# Cycle-Controller-Onboard.net
KiCad netlist of a schematic drawn in Altium Designer
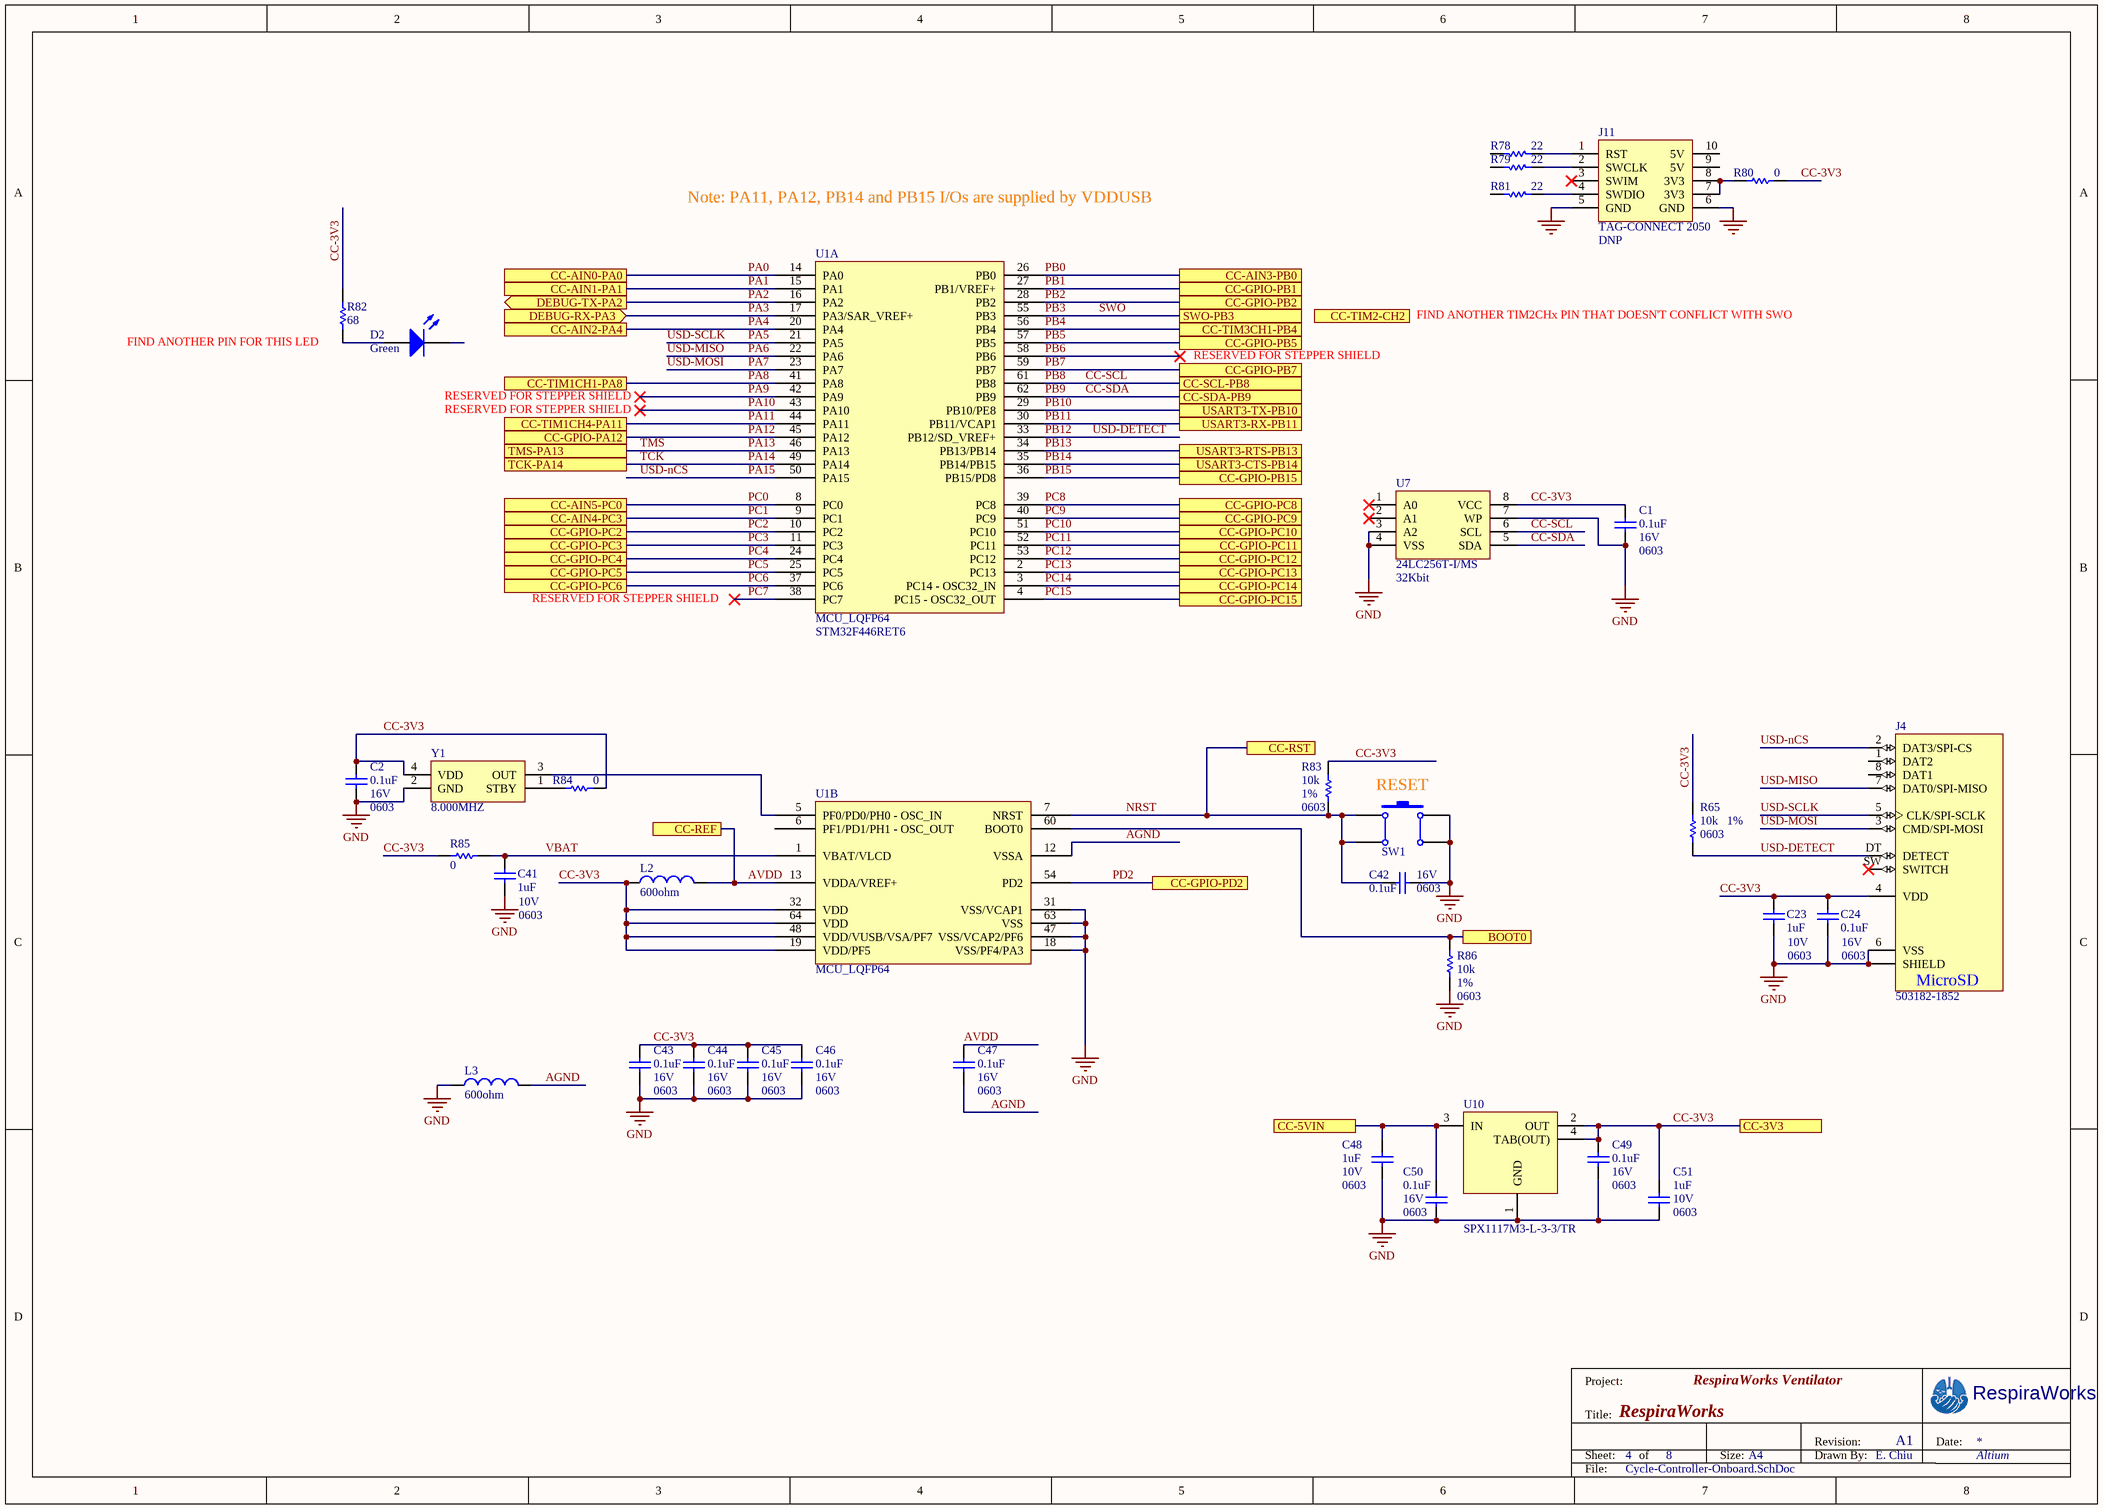
[diagram p0: Cycle-Controller-Onboard.SchDoc]

(export (version "E")
  (design (tool "Eeschema 10.0.6"))
  (components
    (comp (ref "C1")
      (value "0.1uF")
      (footprint "CAP0603")
      (description "Cap 0603")
      (fields
        (field (name "MANUFACTURER") "Yageo")
        (field (name "VOLTAGE") "16V")
        (field (name "PCB PACKAGE") "0603")
        (field (name "Comment") "CAP 0603")
      )
      (libsource (lib "generic") (part "CAP 0603"))
    )
    (comp (ref "C2")
      (value "0.1uF")
      (footprint "CAP0603")
      (description "Cap 0603")
      (fields
        (field (name "MANUFACTURER") "Yageo")
        (field (name "VOLTAGE") "16V")
        (field (name "PCB PACKAGE") "0603")
        (field (name "Comment") "CAP 0603")
      )
      (libsource (lib "generic") (part "CAP 0603"))
    )
    (comp (ref "C23")
      (value "1uF")
      (footprint "CAP0603")
      (description "Cap 0603")
      (fields
        (field (name "MANUFACTURER") "Yageo")
        (field (name "VOLTAGE") "10V")
        (field (name "PCB PACKAGE") "0603")
        (field (name "Comment") "CAP 0603")
      )
      (libsource (lib "generic") (part "CAP 0603"))
    )
    (comp (ref "C24")
      (value "0.1uF")
      (footprint "CAP0603")
      (description "Cap 0603")
      (fields
        (field (name "MANUFACTURER") "Yageo")
        (field (name "VOLTAGE") "16V")
        (field (name "PCB PACKAGE") "0603")
        (field (name "Comment") "CAP 0603")
      )
      (libsource (lib "generic") (part "CAP 0603"))
    )
    (comp (ref "C41")
      (value "1uF")
      (footprint "CAP0603")
      (description "Cap 0603")
      (fields
        (field (name "MANUFACTURER") "Yageo")
        (field (name "VOLTAGE") "10V")
        (field (name "PCB PACKAGE") "0603")
        (field (name "Comment") "CAP 0603")
      )
      (libsource (lib "generic") (part "CAP 0603"))
    )
    (comp (ref "C42")
      (value "0.1uF")
      (footprint "CAP0603")
      (description "Cap 0603")
      (fields
        (field (name "MANUFACTURER") "Yageo")
        (field (name "VOLTAGE") "16V")
        (field (name "PCB PACKAGE") "0603")
        (field (name "Comment") "CAP 0603")
      )
      (libsource (lib "generic") (part "CAP 0603"))
    )
    (comp (ref "C43")
      (value "0.1uF")
      (footprint "CAP0603")
      (description "Cap 0603")
      (fields
        (field (name "MANUFACTURER") "Yageo")
        (field (name "VOLTAGE") "16V")
        (field (name "PCB PACKAGE") "0603")
        (field (name "Comment") "CAP 0603")
      )
      (libsource (lib "generic") (part "CAP 0603"))
    )
    (comp (ref "C44")
      (value "0.1uF")
      (footprint "CAP0603")
      (description "Cap 0603")
      (fields
        (field (name "MANUFACTURER") "Yageo")
        (field (name "VOLTAGE") "16V")
        (field (name "PCB PACKAGE") "0603")
        (field (name "Comment") "CAP 0603")
      )
      (libsource (lib "generic") (part "CAP 0603"))
    )
    (comp (ref "C45")
      (value "0.1uF")
      (footprint "CAP0603")
      (description "Cap 0603")
      (fields
        (field (name "MANUFACTURER") "Yageo")
        (field (name "VOLTAGE") "16V")
        (field (name "PCB PACKAGE") "0603")
        (field (name "Comment") "CAP 0603")
      )
      (libsource (lib "generic") (part "CAP 0603"))
    )
    (comp (ref "C46")
      (value "0.1uF")
      (footprint "CAP0603")
      (description "Cap 0603")
      (fields
        (field (name "MANUFACTURER") "Yageo")
        (field (name "VOLTAGE") "16V")
        (field (name "PCB PACKAGE") "0603")
        (field (name "Comment") "CAP 0603")
      )
      (libsource (lib "generic") (part "CAP 0603"))
    )
    (comp (ref "C47")
      (value "0.1uF")
      (footprint "CAP0603")
      (description "Cap 0603")
      (fields
        (field (name "MANUFACTURER") "Yageo")
        (field (name "VOLTAGE") "16V")
        (field (name "PCB PACKAGE") "0603")
        (field (name "Comment") "CAP 0603")
      )
      (libsource (lib "generic") (part "CAP 0603"))
    )
    (comp (ref "C48")
      (value "1uF")
      (footprint "CAP0603")
      (description "Cap 0603")
      (fields
        (field (name "MANUFACTURER") "Yageo")
        (field (name "VOLTAGE") "10V")
        (field (name "PCB PACKAGE") "0603")
        (field (name "Comment") "CAP 0603")
      )
      (libsource (lib "generic") (part "CAP 0603"))
    )
    (comp (ref "C49")
      (value "0.1uF")
      (footprint "CAP0603")
      (description "Cap 0603")
      (fields
        (field (name "MANUFACTURER") "Yageo")
        (field (name "VOLTAGE") "16V")
        (field (name "PCB PACKAGE") "0603")
        (field (name "Comment") "CAP 0603")
      )
      (libsource (lib "generic") (part "CAP 0603"))
    )
    (comp (ref "C50")
      (value "0.1uF")
      (footprint "CAP0603")
      (description "Cap 0603")
      (fields
        (field (name "MANUFACTURER") "Yageo")
        (field (name "VOLTAGE") "16V")
        (field (name "PCB PACKAGE") "0603")
        (field (name "Comment") "CAP 0603")
      )
      (libsource (lib "generic") (part "CAP 0603"))
    )
    (comp (ref "C51")
      (value "1uF")
      (footprint "CAP0603")
      (description "Cap 0603")
      (fields
        (field (name "MANUFACTURER") "Yageo")
        (field (name "VOLTAGE") "10V")
        (field (name "PCB PACKAGE") "0603")
        (field (name "Comment") "CAP 0603")
      )
      (libsource (lib "generic") (part "CAP 0603"))
    )
    (comp (ref "D2")
      (value "Green")
      (footprint "LED0603")
      (description "LED 0603")
      (fields (field (name "MANUFACTURER") "Lite-On"))
      (libsource (lib "generic") (part "LED 0603"))
    )
    (comp (ref "J4")
      (value "503182-1852")
      (footprint "molex:503182-1852")
      (description "10 _8 + 2_ Position Card Connector microSD Surface Mount, Right Angle Gold")
      (fields (field (name "MANUFACTURER") "Molex") (field (name "DIGI-KEY_PART_NUMBER") "WM12834CT-ND"))
      (libsource (lib "molex") (part "503182-1852"))
    )
    (comp (ref "J11")
      (value "TAG-CONNECT 2050")
      (footprint "TAG-CONNECT-2050")
      (description "10-pin TAG-CONNECT Bed of Nails footprint")
      (fields (field (name "MANUFACTURER") "TAG-CONNECT") (field (name "DO NOT POPULATE") "DNP"))
      (libsource (lib "special") (part "TC-2050-STLINK"))
    )
    (comp (ref "L2")
      (value "600ohm")
      (footprint "IND0603")
      (description "Ferrite 0603")
      (fields (field (name "MANUFACTURER") "Wurth") (field (name "Comment") "BEAD"))
      (libsource (lib "generic") (part "FERRITE 0603"))
    )
    (comp (ref "L3")
      (value "600ohm")
      (footprint "IND0603")
      (description "Ferrite 0603")
      (fields (field (name "MANUFACTURER") "Wurth") (field (name "Comment") "BEAD"))
      (libsource (lib "generic") (part "FERRITE 0603"))
    )
    (comp (ref "R65")
      (value "10k")
      (footprint "RES0603")
      (description "Res 0603")
      (fields
        (field (name "MANUFACTURER") "Panasonic")
        (field (name "PCB PACKAGE") "0603")
        (field (name "TOLERANCE") "1%")
        (field (name "Comment") "RES 0603")
      )
      (libsource (lib "generic") (part "RES 0603"))
    )
    (comp (ref "R78")
      (value "22")
      (footprint "RES0603")
      (description "Res 0603")
      (fields (field (name "MANUFACTURER") "Yageo") (field (name "TOLERANCE") "1%"))
      (libsource (lib "generic") (part "RES 0603"))
    )
    (comp (ref "R79")
      (value "22")
      (footprint "RES0603")
      (description "Res 0603")
      (fields (field (name "MANUFACTURER") "Yageo") (field (name "TOLERANCE") "1%"))
      (libsource (lib "generic") (part "RES 0603"))
    )
    (comp (ref "R80")
      (value "0")
      (footprint "RES0603")
      (description "Res 0603")
      (fields (field (name "MANUFACTURER") "Panasonic") (field (name "Comment") "RES 0603"))
      (libsource (lib "generic") (part "RES 0603"))
    )
    (comp (ref "R81")
      (value "22")
      (footprint "RES0603")
      (description "Res 0603")
      (fields (field (name "MANUFACTURER") "Yageo") (field (name "TOLERANCE") "1%"))
      (libsource (lib "generic") (part "RES 0603"))
    )
    (comp (ref "R82")
      (value "68")
      (footprint "RES0603")
      (description "Res 0603")
      (fields (field (name "MANUFACTURER") "Panasonic") (field (name "TOLERANCE") "1%"))
      (libsource (lib "generic") (part "RES 0603"))
    )
    (comp (ref "R83")
      (value "10k")
      (footprint "RES0603")
      (description "Res 0603")
      (fields
        (field (name "MANUFACTURER") "Panasonic")
        (field (name "PCB PACKAGE") "0603")
        (field (name "TOLERANCE") "1%")
        (field (name "Comment") "RES 0603")
      )
      (libsource (lib "generic") (part "RES 0603"))
    )
    (comp (ref "R84")
      (value "0")
      (footprint "RES0603")
      (description "Res 0603")
      (fields (field (name "MANUFACTURER") "Panasonic") (field (name "Comment") "RES 0603"))
      (libsource (lib "generic") (part "RES 0603"))
    )
    (comp (ref "R85")
      (value "0")
      (footprint "RES0603")
      (description "Res 0603")
      (fields (field (name "MANUFACTURER") "Panasonic") (field (name "Comment") "RES 0603"))
      (libsource (lib "generic") (part "RES 0603"))
    )
    (comp (ref "R86")
      (value "10k")
      (footprint "RES0603")
      (description "Res 0603")
      (fields
        (field (name "MANUFACTURER") "Panasonic")
        (field (name "PCB PACKAGE") "0603")
        (field (name "TOLERANCE") "1%")
        (field (name "Comment") "RES 0603")
      )
      (libsource (lib "generic") (part "RES 0603"))
    )
    (comp (ref "SW1")
      (value "BUTTON")
      (footprint "PB-6MM-J-LEAD")
      (description "PUSHBUTTON, 6MM SQ, TACT, J-Lead")
      (fields (field (name "MANUFACTURER") "E-Switch"))
      (libsource (lib "e-switch") (part "PUSHBUTTON-SQ-6MM-TACT-J-LEAD"))
    )
    (comp (ref "U1")
      (value "MCU_LQFP64")
      (footprint "64-LQFP")
      (description "IC MCU 32BIT 512KB FLASH 64LQFP")
      (fields (field (name "MANUFACTURER P/N") "STM32F446RET6") (field (name "MANUFACTURER") "ST Micro"))
      (libsource (lib "Nucleo_64") (part "MCU_LQFP64"))
    )
    (comp (ref "U7")
      (value "32Kbit")
      (footprint "8-MSOP")
      (description "IC EEPROM 256KBIT I2C 400KHZ 8MSOP")
      (fields
        (field (name "MANUFACTURER") "Microchip")
        (field (name "TOLERANCE") "25ppm")
        (field (name "MANUFACTURER P/N") "24LC256T-I/MS")
      )
      (libsource (lib "microchip") (part "24LC256T-I/MS"))
    )
    (comp (ref "U10")
      (value "NCP1117ST33T3G")
      (footprint "3-SOT223")
      (description "LDO, 3.3V out, 1A, 20V in, SOT-223, 0.8W Pd max")
      (fields (field (name "MANUFACTURER") "Exar") (field (name "MANUFACTURER P/N") "SPX1117M3-L-3-3/TR"))
      (libsource (lib "on-semi") (part "NCP1117ST33T3G"))
    )
    (comp (ref "Y1")
      (value "8.000MHZ")
      (footprint "4-OSC3225")
      (description "OSC MEMS 8.000MHZ CMOS SMD")
      (fields (field (name "MANUFACTURER") "Abracon") (field (name "TOLERANCE") "50ppm"))
      (libsource (lib "abracon") (part "ASEMB-8.000MHZ-LC-T"))
    )
  )
  (nets
    (net (code "1") (name "/AGND") (class "Default")
      (node (ref "C47") (pin "2") (pinfunction "2_2") (pintype "passive"))
      (node (ref "L3") (pin "2") (pinfunction "2_2") (pintype "passive"))
      (node (ref "U1") (pin "12") (pinfunction "VSSA_12") (pintype "passive"))
    )
    (net (code "2") (name "/AVDD") (class "Default")
      (node (ref "C47") (pin "1") (pinfunction "1_1") (pintype "passive"))
      (node (ref "L2") (pin "2") (pinfunction "2_2") (pintype "passive"))
      (node (ref "U1") (pin "13") (pinfunction "VDDA/VREF+_13") (pintype "passive"))
    )
    (net (code "3") (name "/BOOT0") (class "Default")
      (node (ref "R86") (pin "2") (pinfunction "2_2") (pintype "passive"))
      (node (ref "U1") (pin "60") (pinfunction "BOOT0_60") (pintype "passive"))
    )
    (net (code "4") (name "/CC-3V3") (class "Default")
      (node (ref "C1") (pin "1") (pinfunction "1_1") (pintype "passive"))
      (node (ref "C2") (pin "1") (pinfunction "1_1") (pintype "passive"))
      (node (ref "C23") (pin "1") (pinfunction "1_1") (pintype "passive"))
      (node (ref "C24") (pin "1") (pinfunction "1_1") (pintype "passive"))
      (node (ref "C43") (pin "1") (pinfunction "1_1") (pintype "passive"))
      (node (ref "C44") (pin "1") (pinfunction "1_1") (pintype "passive"))
      (node (ref "C45") (pin "1") (pinfunction "1_1") (pintype "passive"))
      (node (ref "C46") (pin "1") (pinfunction "1_1") (pintype "passive"))
      (node (ref "C49") (pin "1") (pinfunction "1_1") (pintype "passive"))
      (node (ref "C51") (pin "1") (pinfunction "1_1") (pintype "passive"))
      (node (ref "J4") (pin "4") (pinfunction "VDD_4") (pintype "power_in"))
      (node (ref "L2") (pin "1") (pinfunction "1_1") (pintype "passive"))
      (node (ref "R65") (pin "2") (pinfunction "2_2") (pintype "passive"))
      (node (ref "R80") (pin "2") (pinfunction "2_2") (pintype "passive"))
      (node (ref "R82") (pin "2") (pinfunction "2_2") (pintype "passive"))
      (node (ref "R83") (pin "2") (pinfunction "2_2") (pintype "passive"))
      (node (ref "R84") (pin "1") (pinfunction "1_1") (pintype "passive"))
      (node (ref "R85") (pin "2") (pinfunction "2_2") (pintype "passive"))
      (node (ref "U1") (pin "19") (pinfunction "VDD/PF5_19") (pintype "passive"))
      (node (ref "U1") (pin "32") (pinfunction "VDD_32") (pintype "passive"))
      (node (ref "U1") (pin "48") (pinfunction "VDD/VUSB/VSA/PF7_48") (pintype "passive"))
      (node (ref "U1") (pin "64") (pinfunction "VDD_64") (pintype "passive"))
      (node (ref "U10") (pin "2") (pinfunction "OUT_2") (pintype "passive"))
      (node (ref "U10") (pin "4") (pinfunction "TAB(OUT)_4") (pintype "passive"))
      (node (ref "U7") (pin "8") (pinfunction "VCC_8") (pintype "passive"))
      (node (ref "Y1") (pin "4") (pinfunction "VDD_4") (pintype "passive"))
    )
    (net (code "5") (name "/CC-5VIN") (class "Default")
      (node (ref "C48") (pin "1") (pinfunction "1_1") (pintype "passive"))
      (node (ref "C50") (pin "1") (pinfunction "1_1") (pintype "passive"))
      (node (ref "U10") (pin "3") (pinfunction "IN_3") (pintype "passive"))
    )
    (net (code "6") (name "/CC-SCL") (class "Default")
      (node (ref "U1") (pin "61") (pinfunction "PB8_61") (pintype "passive"))
      (node (ref "U7") (pin "6") (pinfunction "SCL_6") (pintype "passive"))
    )
    (net (code "7") (name "/CC-SDA") (class "Default")
      (node (ref "U1") (pin "62") (pinfunction "PB9_62") (pintype "passive"))
      (node (ref "U7") (pin "5") (pinfunction "SDA_5") (pintype "passive"))
    )
    (net (code "9") (name "/NRST") (class "Default")
      (node (ref "C42") (pin "1") (pinfunction "1_1") (pintype "passive"))
      (node (ref "R83") (pin "1") (pinfunction "1_1") (pintype "passive"))
      (node (ref "SW1") (pin "1") (pinfunction "1_1") (pintype "passive"))
      (node (ref "SW1") (pin "2") (pinfunction "2_2") (pintype "passive"))
      (node (ref "U1") (pin "7") (pinfunction "NRST_7") (pintype "passive"))
    )
    (net (code "10") (name "/PA0") (class "Default")
      (node (ref "U1") (pin "14") (pinfunction "PA0_14") (pintype "passive"))
    )
    (net (code "11") (name "/PA1") (class "Default")
      (node (ref "U1") (pin "15") (pinfunction "PA1_15") (pintype "passive"))
    )
    (net (code "12") (name "/PA2") (class "Default")
      (node (ref "U1") (pin "16") (pinfunction "PA2_16") (pintype "passive"))
    )
    (net (code "13") (name "/PA3") (class "Default")
      (node (ref "U1") (pin "17") (pinfunction "PA3/SAR_VREF+_17") (pintype "passive"))
    )
    (net (code "14") (name "/PA4") (class "Default")
      (node (ref "U1") (pin "20") (pinfunction "PA4_20") (pintype "passive"))
    )
    (net (code "15") (name "/PA5") (class "Default")
      (node (ref "J4") (pin "5") (pinfunction "CLK/SPI-SCLK_5") (pintype "bidirectional"))
      (node (ref "U1") (pin "21") (pinfunction "PA5_21") (pintype "passive"))
    )
    (net (code "16") (name "/PA6") (class "Default")
      (node (ref "J4") (pin "7") (pinfunction "DAT0/SPI-MISO_7") (pintype "bidirectional"))
      (node (ref "U1") (pin "22") (pinfunction "PA6_22") (pintype "passive"))
    )
    (net (code "17") (name "/PA7") (class "Default")
      (node (ref "J4") (pin "3") (pinfunction "CMD/SPI-MOSI_3") (pintype "bidirectional"))
      (node (ref "U1") (pin "23") (pinfunction "PA7_23") (pintype "passive"))
    )
    (net (code "18") (name "/PA8") (class "Default")
      (node (ref "U1") (pin "41") (pinfunction "PA8_41") (pintype "passive"))
    )
    (net (code "19") (name "/PA9") (class "Default")
      (node (ref "U1") (pin "42") (pinfunction "PA9_42") (pintype "passive+no_connect"))
    )
    (net (code "20") (name "/PA10") (class "Default")
      (node (ref "U1") (pin "43") (pinfunction "PA10_43") (pintype "passive+no_connect"))
    )
    (net (code "21") (name "/PA11") (class "Default")
      (node (ref "U1") (pin "44") (pinfunction "PA11_44") (pintype "passive"))
    )
    (net (code "22") (name "/PA12") (class "Default")
      (node (ref "U1") (pin "45") (pinfunction "PA12_45") (pintype "passive"))
    )
    (net (code "23") (name "/PA13") (class "Default")
      (node (ref "U1") (pin "46") (pinfunction "PA13_46") (pintype "passive"))
    )
    (net (code "24") (name "/PA14") (class "Default")
      (node (ref "U1") (pin "49") (pinfunction "PA14_49") (pintype "passive"))
    )
    (net (code "25") (name "/PA15") (class "Default")
      (node (ref "J4") (pin "2") (pinfunction "DAT3/SPI-CS_2") (pintype "bidirectional"))
      (node (ref "U1") (pin "50") (pinfunction "PA15_50") (pintype "passive"))
    )
    (net (code "26") (name "/PB0") (class "Default")
      (node (ref "U1") (pin "26") (pinfunction "PB0_26") (pintype "passive"))
    )
    (net (code "27") (name "/PB1") (class "Default")
      (node (ref "U1") (pin "27") (pinfunction "PB1/VREF+_27") (pintype "passive"))
    )
    (net (code "28") (name "/PB2") (class "Default")
      (node (ref "U1") (pin "28") (pinfunction "PB2_28") (pintype "passive"))
    )
    (net (code "29") (name "/PB3") (class "Default")
      (node (ref "U1") (pin "55") (pinfunction "PB3_55") (pintype "passive"))
    )
    (net (code "30") (name "/PB4") (class "Default")
      (node (ref "U1") (pin "56") (pinfunction "PB4_56") (pintype "passive"))
    )
    (net (code "31") (name "/PB5") (class "Default")
      (node (ref "U1") (pin "57") (pinfunction "PB5_57") (pintype "passive"))
    )
    (net (code "32") (name "/PB6") (class "Default")
      (node (ref "U1") (pin "58") (pinfunction "PB6_58") (pintype "passive+no_connect"))
    )
    (net (code "33") (name "/PB7") (class "Default")
      (node (ref "U1") (pin "59") (pinfunction "PB7_59") (pintype "passive"))
    )
    (net (code "34") (name "/PB10") (class "Default")
      (node (ref "U1") (pin "29") (pinfunction "PB10/PE8_29") (pintype "passive"))
    )
    (net (code "35") (name "/PB11") (class "Default")
      (node (ref "U1") (pin "30") (pinfunction "PB11/VCAP1_30") (pintype "passive"))
    )
    (net (code "36") (name "/PB12") (class "Default")
      (node (ref "J4") (pin "DT") (pinfunction "DETECT_DT") (pintype "bidirectional"))
      (node (ref "R65") (pin "1") (pinfunction "1_1") (pintype "passive"))
      (node (ref "U1") (pin "33") (pinfunction "PB12/SD_VREF+_33") (pintype "passive"))
    )
    (net (code "37") (name "/PB13") (class "Default")
      (node (ref "U1") (pin "34") (pinfunction "PB13/PB14_34") (pintype "passive"))
    )
    (net (code "38") (name "/PB14") (class "Default")
      (node (ref "U1") (pin "35") (pinfunction "PB14/PB15_35") (pintype "passive"))
    )
    (net (code "39") (name "/PB15") (class "Default")
      (node (ref "U1") (pin "36") (pinfunction "PB15/PD8_36") (pintype "passive"))
    )
    (net (code "40") (name "/PC0") (class "Default")
      (node (ref "U1") (pin "8") (pinfunction "PC0_8") (pintype "passive"))
    )
    (net (code "41") (name "/PC1") (class "Default")
      (node (ref "U1") (pin "9") (pinfunction "PC1_9") (pintype "passive"))
    )
    (net (code "42") (name "/PC2") (class "Default")
      (node (ref "U1") (pin "10") (pinfunction "PC2_10") (pintype "passive"))
    )
    (net (code "43") (name "/PC3") (class "Default")
      (node (ref "U1") (pin "11") (pinfunction "PC3_11") (pintype "passive"))
    )
    (net (code "44") (name "/PC4") (class "Default")
      (node (ref "U1") (pin "24") (pinfunction "PC4_24") (pintype "passive"))
    )
    (net (code "45") (name "/PC5") (class "Default")
      (node (ref "U1") (pin "25") (pinfunction "PC5_25") (pintype "passive"))
    )
    (net (code "46") (name "/PC6") (class "Default")
      (node (ref "U1") (pin "37") (pinfunction "PC6_37") (pintype "passive"))
    )
    (net (code "47") (name "/PC7") (class "Default")
      (node (ref "U1") (pin "38") (pinfunction "PC7_38") (pintype "passive+no_connect"))
    )
    (net (code "48") (name "/PC8") (class "Default")
      (node (ref "U1") (pin "39") (pinfunction "PC8_39") (pintype "passive"))
    )
    (net (code "49") (name "/PC9") (class "Default")
      (node (ref "U1") (pin "40") (pinfunction "PC9_40") (pintype "passive"))
    )
    (net (code "50") (name "/PC10") (class "Default")
      (node (ref "U1") (pin "51") (pinfunction "PC10_51") (pintype "passive"))
    )
    (net (code "51") (name "/PC11") (class "Default")
      (node (ref "U1") (pin "52") (pinfunction "PC11_52") (pintype "passive"))
    )
    (net (code "52") (name "/PC12") (class "Default")
      (node (ref "U1") (pin "53") (pinfunction "PC12_53") (pintype "passive"))
    )
    (net (code "53") (name "/PC13") (class "Default")
      (node (ref "U1") (pin "2") (pinfunction "PC13_2") (pintype "passive"))
    )
    (net (code "54") (name "/PC14") (class "Default")
      (node (ref "U1") (pin "3") (pinfunction "PC14_-_OSC32_IN_3") (pintype "passive"))
    )
    (net (code "55") (name "/PC15") (class "Default")
      (node (ref "U1") (pin "4") (pinfunction "PC15_-_OSC32_OUT_4") (pintype "passive"))
    )
    (net (code "56") (name "/PD2") (class "Default")
      (node (ref "U1") (pin "54") (pinfunction "PD2_54") (pintype "passive"))
    )
    (net (code "57") (name "/VBAT") (class "Default")
      (node (ref "C41") (pin "1") (pinfunction "1_1") (pintype "passive"))
      (node (ref "R85") (pin "1") (pinfunction "1_1") (pintype "passive"))
      (node (ref "U1") (pin "1") (pinfunction "VBAT/VLCD_1") (pintype "passive"))
    )
    (net (code "58") (name "GND") (class "Default")
      (node (ref "C1") (pin "2") (pinfunction "2_2") (pintype "passive"))
      (node (ref "C2") (pin "2") (pinfunction "2_2") (pintype "passive"))
      (node (ref "C23") (pin "2") (pinfunction "2_2") (pintype "passive"))
      (node (ref "C24") (pin "2") (pinfunction "2_2") (pintype "passive"))
      (node (ref "C41") (pin "2") (pinfunction "2_2") (pintype "passive"))
      (node (ref "C42") (pin "2") (pinfunction "2_2") (pintype "passive"))
      (node (ref "C43") (pin "2") (pinfunction "2_2") (pintype "passive"))
      (node (ref "C44") (pin "2") (pinfunction "2_2") (pintype "passive"))
      (node (ref "C45") (pin "2") (pinfunction "2_2") (pintype "passive"))
      (node (ref "C46") (pin "2") (pinfunction "2_2") (pintype "passive"))
      (node (ref "C48") (pin "2") (pinfunction "2_2") (pintype "passive"))
      (node (ref "C49") (pin "2") (pinfunction "2_2") (pintype "passive"))
      (node (ref "C50") (pin "2") (pinfunction "2_2") (pintype "passive"))
      (node (ref "C51") (pin "2") (pinfunction "2_2") (pintype "passive"))
      (node (ref "J11") (pin "5") (pinfunction "GND_5") (pintype "passive"))
      (node (ref "J11") (pin "6") (pinfunction "GND_6") (pintype "passive"))
      (node (ref "J4") (pin "6") (pinfunction "VSS_6") (pintype "power_in"))
      (node (ref "J4") (pin "P1") (pinfunction "SHIELD_P1") (pintype "passive"))
      (node (ref "J4") (pin "P2") (pinfunction "SHIELD_P2") (pintype "passive"))
      (node (ref "J4") (pin "P3") (pinfunction "SHIELD_P3") (pintype "passive"))
      (node (ref "J4") (pin "P4") (pinfunction "SHIELD_P4") (pintype "passive"))
      (node (ref "J4") (pin "P5") (pinfunction "SHIELD_P5") (pintype "passive"))
      (node (ref "L3") (pin "1") (pinfunction "1_1") (pintype "passive"))
      (node (ref "R86") (pin "1") (pinfunction "1_1") (pintype "passive"))
      (node (ref "SW1") (pin "3") (pinfunction "3_3") (pintype "passive"))
      (node (ref "SW1") (pin "4") (pinfunction "4_4") (pintype "passive"))
      (node (ref "U1") (pin "18") (pinfunction "VSS/PF4/PA3_18") (pintype "passive"))
      (node (ref "U1") (pin "31") (pinfunction "VSS/VCAP1_31") (pintype "passive"))
      (node (ref "U1") (pin "47") (pinfunction "VSS/VCAP2/PF6_47") (pintype "passive"))
      (node (ref "U1") (pin "63") (pinfunction "VSS_63") (pintype "passive"))
      (node (ref "U10") (pin "1") (pinfunction "GND_1") (pintype "passive"))
      (node (ref "U7") (pin "3") (pinfunction "A2_3") (pintype "passive"))
      (node (ref "U7") (pin "4") (pinfunction "VSS_4") (pintype "passive"))
      (node (ref "U7") (pin "7") (pinfunction "WP_7") (pintype "passive"))
      (node (ref "Y1") (pin "2") (pinfunction "GND_2") (pintype "passive"))
    )
    (net (code "59") (name "Net-(D2-PadA)") (class "Default")
      (node (ref "D2") (pin "A") (pinfunction "A_A") (pintype "passive"))
      (node (ref "R82") (pin "1") (pinfunction "1_1") (pintype "passive"))
    )
    (net (code "60") (name "Net-(J11-3V3-Pad7)") (class "Default")
      (node (ref "J11") (pin "7") (pinfunction "3V3_7") (pintype "passive"))
      (node (ref "J11") (pin "8") (pinfunction "3V3_8") (pintype "passive"))
      (node (ref "R80") (pin "1") (pinfunction "1_1") (pintype "passive"))
    )
    (net (code "61") (name "Net-(J11-RST)") (class "Default")
      (node (ref "J11") (pin "1") (pinfunction "RST_1") (pintype "passive"))
      (node (ref "R78") (pin "1") (pinfunction "1_1") (pintype "passive"))
    )
    (net (code "62") (name "Net-(J11-SWCLK)") (class "Default")
      (node (ref "J11") (pin "2") (pinfunction "SWCLK_2") (pintype "passive"))
      (node (ref "R79") (pin "1") (pinfunction "1_1") (pintype "passive"))
    )
    (net (code "63") (name "Net-(J11-SWDIO)") (class "Default")
      (node (ref "J11") (pin "4") (pinfunction "SWDIO_4") (pintype "passive"))
      (node (ref "R81") (pin "1") (pinfunction "1_1") (pintype "passive"))
    )
    (net (code "64") (name "Net-(U1B-PF0{slash}PD0{slash}PH0_-_OSC_IN)") (class "Default")
      (node (ref "U1") (pin "5") (pinfunction "PF0/PD0/PH0_-_OSC_IN_5") (pintype "passive"))
      (node (ref "Y1") (pin "3") (pinfunction "OUT_3") (pintype "passive"))
    )
    (net (code "65") (name "Net-(Y1-STBY)") (class "Default")
      (node (ref "R84") (pin "2") (pinfunction "2_2") (pintype "passive"))
      (node (ref "Y1") (pin "1") (pinfunction "STBY_1") (pintype "passive"))
    )
    (net (code "66") (name "unconnected-(D2-PadK)") (class "Default")
      (node (ref "D2") (pin "K") (pinfunction "K_K") (pintype "passive"))
    )
    (net (code "67") (name "unconnected-(J4-DAT1-Pad8)") (class "Default")
      (node (ref "J4") (pin "8") (pinfunction "DAT1_8") (pintype "bidirectional"))
    )
    (net (code "68") (name "unconnected-(J4-DAT2-Pad1)") (class "Default")
      (node (ref "J4") (pin "1") (pinfunction "DAT2_1") (pintype "bidirectional"))
    )
    (net (code "69") (name "unconnected-(J4-SWITCH-PadSW)") (class "Default")
      (node (ref "J4") (pin "SW") (pinfunction "SWITCH_SW") (pintype "bidirectional+no_connect"))
    )
    (net (code "70") (name "unconnected-(J11-5V-Pad9)") (class "Default")
      (node (ref "J11") (pin "9") (pinfunction "5V_9") (pintype "passive"))
    )
    (net (code "71") (name "unconnected-(J11-5V-Pad10)") (class "Default")
      (node (ref "J11") (pin "10") (pinfunction "5V_10") (pintype "passive"))
    )
    (net (code "72") (name "unconnected-(J11-SWIM-Pad3)") (class "Default")
      (node (ref "J11") (pin "3") (pinfunction "SWIM_3") (pintype "passive+no_connect"))
    )
    (net (code "73") (name "unconnected-(R78-Pad2)") (class "Default")
      (node (ref "R78") (pin "2") (pinfunction "2_2") (pintype "passive"))
    )
    (net (code "74") (name "unconnected-(R79-Pad2)") (class "Default")
      (node (ref "R79") (pin "2") (pinfunction "2_2") (pintype "passive"))
    )
    (net (code "75") (name "unconnected-(R81-Pad2)") (class "Default")
      (node (ref "R81") (pin "2") (pinfunction "2_2") (pintype "passive"))
    )
    (net (code "76") (name "unconnected-(U1B-PF1{slash}PD1{slash}PH1_-_OSC_OUT-Pad6)") (class "Default")
      (node (ref "U1") (pin "6") (pinfunction "PF1/PD1/PH1_-_OSC_OUT_6") (pintype "passive"))
    )
    (net (code "77") (name "unconnected-(U7-A0-Pad1)") (class "Default")
      (node (ref "U7") (pin "1") (pinfunction "A0_1") (pintype "passive+no_connect"))
    )
    (net (code "78") (name "unconnected-(U7-A1-Pad2)") (class "Default")
      (node (ref "U7") (pin "2") (pinfunction "A1_2") (pintype "passive+no_connect"))
    )
  )
)
